# AMX30.net
KiCad netlist of a schematic drawn in Altium Designer
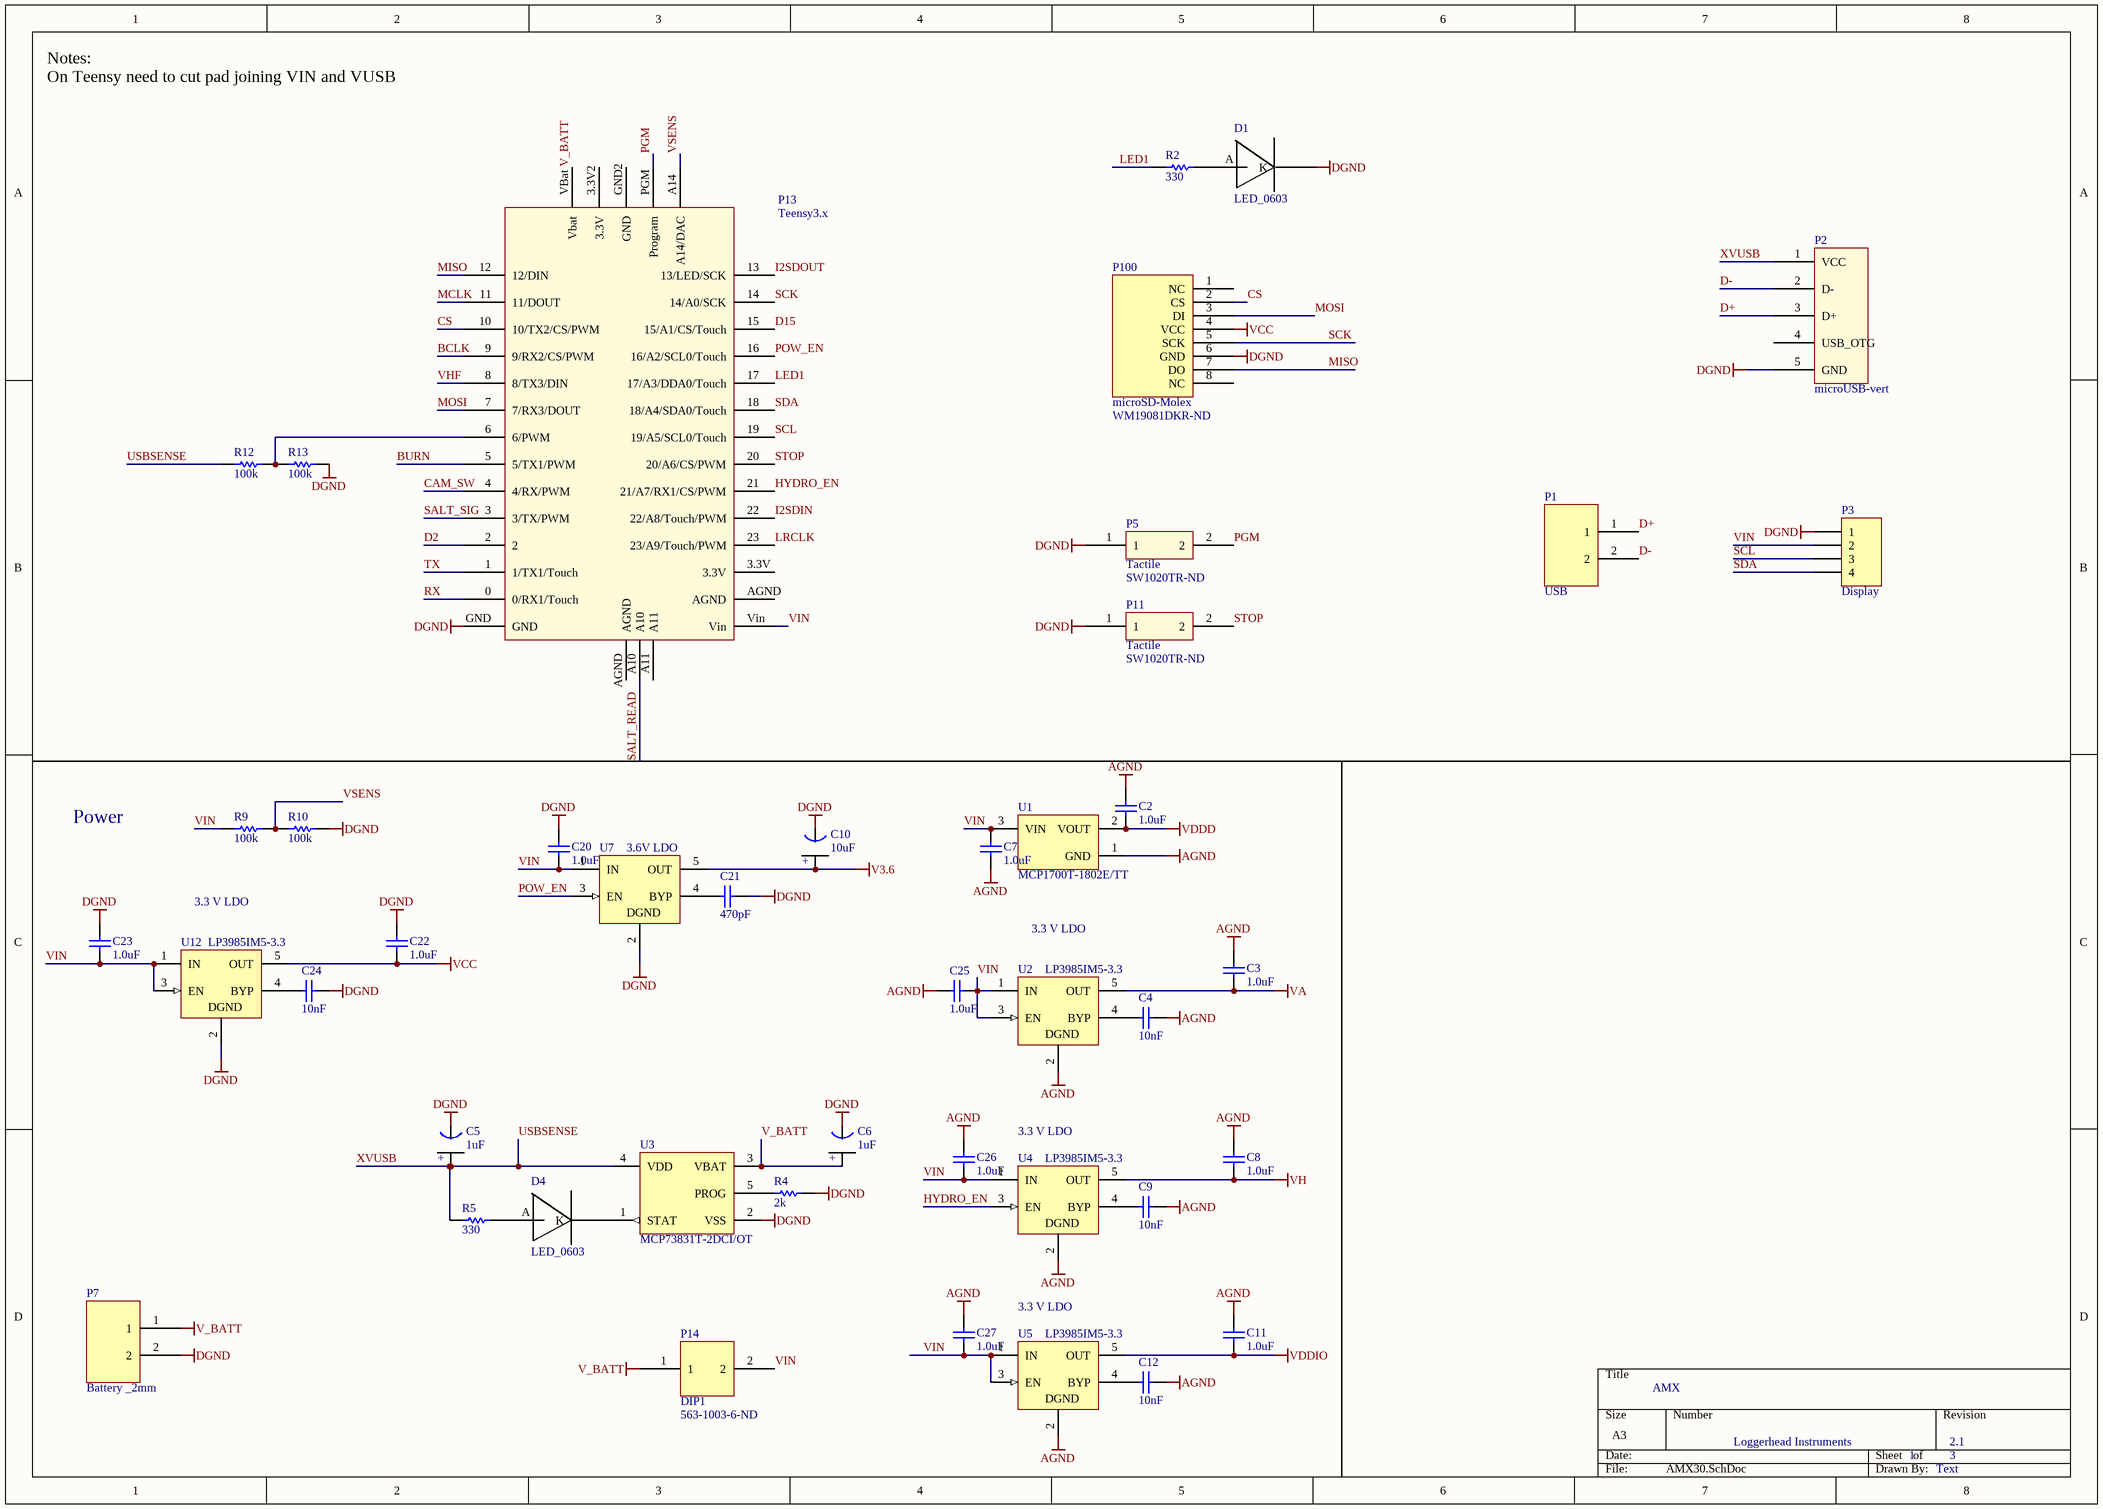
[diagram p0: AMX30.SchDoc]

(export (version "E")
  (design (tool "Eeschema 10.0.6"))
  (components
    (comp (ref "C2")
      (value "1.0uF")
      (footprint "0402")
      (description "Ceramic Chip Capacitor - Standard")
      (fields (field (name "PUBLISHER") "Altium Limited"))
      (libsource (lib "KEMET Chip Capacitor") (part "C0402"))
    )
    (comp (ref "C3")
      (value "1.0uF")
      (footprint "0402")
      (description "Ceramic Chip Capacitor - Standard")
      (fields (field (name "PUBLISHER") "Altium Limited"))
      (libsource (lib "KEMET Chip Capacitor") (part "C0402"))
    )
    (comp (ref "C4")
      (value "10nF")
      (footprint "0402")
      (description "Ceramic Chip Capacitor - Standard")
      (fields (field (name "PUBLISHER") "Altium Limited"))
      (libsource (lib "KEMET Chip Capacitor") (part "C0402"))
    )
    (comp (ref "C5") (value "1uF") (footprint "Tant0805") (libsource (lib "Loggerhead") (part "Tant0805")))
    (comp (ref "C6") (value "1uF") (footprint "Tant0805") (libsource (lib "Loggerhead") (part "Tant0805")))
    (comp (ref "C7")
      (value "1.0uF")
      (footprint "0402")
      (description "Ceramic Chip Capacitor - Standard")
      (fields (field (name "PUBLISHER") "Altium Limited"))
      (libsource (lib "KEMET Chip Capacitor") (part "C0402"))
    )
    (comp (ref "C8")
      (value "1.0uF")
      (footprint "0402")
      (description "Ceramic Chip Capacitor - Standard")
      (fields (field (name "PUBLISHER") "Altium Limited"))
      (libsource (lib "KEMET Chip Capacitor") (part "C0402"))
    )
    (comp (ref "C9")
      (value "10nF")
      (footprint "0402")
      (description "Ceramic Chip Capacitor - Standard")
      (fields (field (name "PUBLISHER") "Altium Limited"))
      (libsource (lib "KEMET Chip Capacitor") (part "C0402"))
    )
    (comp (ref "C10") (value "10uF") (footprint "Tant0805") (libsource (lib "Loggerhead") (part "Tant0805")))
    (comp (ref "C11")
      (value "1.0uF")
      (footprint "0402")
      (description "Ceramic Chip Capacitor - Standard")
      (fields (field (name "PUBLISHER") "Altium Limited"))
      (libsource (lib "KEMET Chip Capacitor") (part "C0402"))
    )
    (comp (ref "C12")
      (value "10nF")
      (footprint "0402")
      (description "Ceramic Chip Capacitor - Standard")
      (fields (field (name "PUBLISHER") "Altium Limited"))
      (libsource (lib "KEMET Chip Capacitor") (part "C0402"))
    )
    (comp (ref "C20")
      (value "1.0uF")
      (footprint "0402")
      (description "Ceramic Chip Capacitor - Standard")
      (fields (field (name "PUBLISHER") "Altium Limited"))
      (libsource (lib "KEMET Chip Capacitor") (part "C0402"))
    )
    (comp (ref "C21")
      (value "470pF")
      (footprint "0402")
      (description "Ceramic Chip Capacitor - Standard")
      (fields (field (name "PUBLISHER") "Altium Limited"))
      (libsource (lib "KEMET Chip Capacitor") (part "C0402"))
    )
    (comp (ref "C22")
      (value "1.0uF")
      (footprint "0402")
      (description "Ceramic Chip Capacitor - Standard")
      (fields (field (name "PUBLISHER") "Altium Limited"))
      (libsource (lib "KEMET Chip Capacitor") (part "C0402"))
    )
    (comp (ref "C23")
      (value "1.0uF")
      (footprint "0402")
      (description "Ceramic Chip Capacitor - Standard")
      (fields (field (name "PUBLISHER") "Altium Limited"))
      (libsource (lib "KEMET Chip Capacitor") (part "C0402"))
    )
    (comp (ref "C24")
      (value "10nF")
      (footprint "0402")
      (description "Ceramic Chip Capacitor - Standard")
      (fields (field (name "PUBLISHER") "Altium Limited"))
      (libsource (lib "KEMET Chip Capacitor") (part "C0402"))
    )
    (comp (ref "C25")
      (value "1.0uF")
      (footprint "0402")
      (description "Ceramic Chip Capacitor - Standard")
      (fields (field (name "PUBLISHER") "Altium Limited"))
      (libsource (lib "KEMET Chip Capacitor") (part "C0402"))
    )
    (comp (ref "C26")
      (value "1.0uF")
      (footprint "0402")
      (description "Ceramic Chip Capacitor - Standard")
      (fields (field (name "PUBLISHER") "Altium Limited"))
      (libsource (lib "KEMET Chip Capacitor") (part "C0402"))
    )
    (comp (ref "C27")
      (value "1.0uF")
      (footprint "0402")
      (description "Ceramic Chip Capacitor - Standard")
      (fields (field (name "PUBLISHER") "Altium Limited"))
      (libsource (lib "KEMET Chip Capacitor") (part "C0402"))
    )
    (comp (ref "D1")
      (value "LED_0603")
      (footprint "Diode0603")
      (libsource (lib "Loggerhead") (part "LED_0603"))
    )
    (comp (ref "D4")
      (value "LED_0603")
      (footprint "Diode0603")
      (libsource (lib "Loggerhead") (part "LED_0603"))
    )
    (comp (ref "P1")
      (value "USB")
      (footprint "HDR_2x1_2mm")
      (description "Charging Connector")
      (libsource (lib "Loggerhead") (part "HDR_2x1_2mm"))
    )
    (comp (ref "P2")
      (value "microUSB-vert")
      (footprint "MICROUSB-VERT")
      (description "Molex 105133-0011")
      (libsource (lib "Loggerhead") (part "microUSB-vert"))
    )
    (comp (ref "P3")
      (value "Display")
      (footprint "HDR1X4")
      (description "Header, 4-Pin")
      (fields (field (name "PUBLISHER") "Altium Limited"))
      (libsource (lib "Miscellaneous Connectors") (part "Header 4"))
    )
    (comp (ref "P5")
      (value "Tactile")
      (footprint "Tactile-B3U-1000")
      (fields (field (name "SUPPLIER PART NUMBER 1") "SW1020TR-ND"))
      (libsource (lib "Loggerhead") (part "Tactile_B3U-1000"))
    )
    (comp (ref "P7")
      (value "Battery _2mm")
      (footprint "HDR_2x1_2mm")
      (description "Charging Connector")
      (libsource (lib "Loggerhead") (part "HDR_2x1_2mm"))
    )
    (comp (ref "P11")
      (value "Tactile")
      (footprint "Tactile-B3U-1000")
      (fields (field (name "SUPPLIER PART NUMBER 1") "SW1020TR-ND"))
      (libsource (lib "Loggerhead") (part "Tactile_B3U-1000"))
    )
    (comp (ref "P13")
      (value "Teensy3.x")
      (footprint "Teensy3.x")
      (libsource (lib "Teensy") (part "Teensy3.x"))
    )
    (comp (ref "P14")
      (value "DIP1")
      (footprint "DIP1")
      (fields (field (name "SUPPLIER PART NUMBER 1") "563-1003-6-ND"))
      (libsource (lib "Loggerhead") (part "DIP1"))
    )
    (comp (ref "P100")
      (value "microSD-Molex")
      (footprint "microSD_Molex_hinged")
      (fields (field (name "SUPPLIER PART NUMBER 1") "WM19081DKR-ND"))
      (libsource (lib "Loggerhead") (part "microSD_Molex_hinged"))
    )
    (comp (ref "R2")
      (value "330")
      (footprint "3-0603")
      (fields (field (name "PUBLISHER") "Altium Limited"))
      (libsource (lib "Panasonic Resistor") (part "ERJ3RK"))
    )
    (comp (ref "R4")
      (value "2k")
      (footprint "3-0603")
      (fields (field (name "PUBLISHER") "Altium Limited"))
      (libsource (lib "Panasonic Resistor") (part "ERJ3RK"))
    )
    (comp (ref "R5")
      (value "330")
      (footprint "3-0603")
      (fields (field (name "PUBLISHER") "Altium Limited"))
      (libsource (lib "Panasonic Resistor") (part "ERJ3RK"))
    )
    (comp (ref "R9")
      (value "100k")
      (footprint "3-0603")
      (fields (field (name "PUBLISHER") "Altium Limited"))
      (libsource (lib "Panasonic Resistor") (part "ERJ3RK"))
    )
    (comp (ref "R10")
      (value "100k")
      (footprint "3-0603")
      (fields (field (name "PUBLISHER") "Altium Limited"))
      (libsource (lib "Panasonic Resistor") (part "ERJ3RK"))
    )
    (comp (ref "R12")
      (value "100k")
      (footprint "3-0603")
      (fields (field (name "PUBLISHER") "Altium Limited"))
      (libsource (lib "Panasonic Resistor") (part "ERJ3RK"))
    )
    (comp (ref "R13")
      (value "100k")
      (footprint "3-0603")
      (fields (field (name "PUBLISHER") "Altium Limited"))
      (libsource (lib "Panasonic Resistor") (part "ERJ3RK"))
    )
    (comp (ref "U1")
      (value "MCP1700T-1802E/TT")
      (footprint "SOT-23-TT3_N")
      (description "Low Quiescent Current LDO, 3-Pin SOT-23, Extended Temperature, Tape and Reel")
      (fields (field (name "MANUFACTURER") "Microchip"))
      (libsource (lib "Microchip Power Management Line Regulator") (part "MCP1700T-1802E/TT"))
    )
    (comp (ref "U2")
      (value "LP3985IM5-3.3")
      (footprint "MF05A_N")
      (description "Micropower, 150mA Low-Noise Ultra Low-Dropout CMOS Voltage Regulator")
      (fields
        (field (name "MANUFACTURER") "National Semiconductor")
        (field (name "DIGIKEYPARTNUMBER") "LP3985IM5-3.3CT-ND")
        (field (name "PUBLISHER") "Altium Limited")
      )
      (libsource (lib "NSC LDO") (part "LP3985IM5-3.3"))
    )
    (comp (ref "U3")
      (value "MCP73831T-2DCI/OT")
      (footprint "SOT-23-OT5_N")
      (libsource (lib "Microchip Power Management Battery Management") (part "MCP73831T-2DCI/OT"))
    )
    (comp (ref "U4")
      (value "LP3985IM5-3.3")
      (footprint "MF05A_N")
      (description "Micropower, 150mA Low-Noise Ultra Low-Dropout CMOS Voltage Regulator")
      (fields
        (field (name "MANUFACTURER") "National Semiconductor")
        (field (name "DIGIKEYPARTNUMBER") "LP3985IM5-3.3CT-ND")
        (field (name "PUBLISHER") "Altium Limited")
      )
      (libsource (lib "NSC LDO") (part "LP3985IM5-3.3"))
    )
    (comp (ref "U5")
      (value "LP3985IM5-3.3")
      (footprint "MF05A_N")
      (description "Micropower, 150mA Low-Noise Ultra Low-Dropout CMOS Voltage Regulator")
      (fields
        (field (name "MANUFACTURER") "National Semiconductor")
        (field (name "DIGIKEYPARTNUMBER") "LP3985IM5-3.3CT-ND")
        (field (name "PUBLISHER") "Altium Limited")
      )
      (libsource (lib "NSC LDO") (part "LP3985IM5-3.3"))
    )
    (comp (ref "U7")
      (value "3.6V LDO")
      (footprint "MF05A_N")
      (description "Micropower, 150mA Low-Noise Ultra Low-Dropout CMOS Voltage Regulator")
      (fields
        (field (name "PARTNUMBER") "LP3985IM5-3.3")
        (field (name "MANUFACTURER") "National Semiconductor")
        (field (name "PUBLISHER") "Altium Limited")
      )
      (libsource (lib "NSC LDO") (part "LP3985IM5-3.3"))
    )
    (comp (ref "U12")
      (value "LP3985IM5-3.3")
      (footprint "MF05A_N")
      (description "Micropower, 150mA Low-Noise Ultra Low-Dropout CMOS Voltage Regulator")
      (fields
        (field (name "MANUFACTURER") "National Semiconductor")
        (field (name "DIGIKEYPARTNUMBER") "LP3985IM5-3.3CT-ND")
        (field (name "PUBLISHER") "Altium Limited")
      )
      (libsource (lib "NSC LDO") (part "LP3985IM5-3.3"))
    )
  )
  (nets
    (net (code "1") (name "/BCLK") (class "Default")
      (node (ref "P13") (pin "9") (pinfunction "9/RX2/CS/PWM_9") (pintype "passive"))
    )
    (net (code "2") (name "/BURN") (class "Default")
      (node (ref "P13") (pin "5") (pinfunction "5/TX1/PWM_5") (pintype "passive"))
    )
    (net (code "3") (name "/CAM_SW") (class "Default")
      (node (ref "P13") (pin "4") (pinfunction "4/RX/PWM_4") (pintype "passive"))
    )
    (net (code "4") (name "/CS") (class "Default")
      (node (ref "P100") (pin "2") (pinfunction "CS_2") (pintype "passive"))
      (node (ref "P13") (pin "10") (pinfunction "10/TX2/CS/PWM_10") (pintype "passive"))
    )
    (net (code "5") (name "/D+") (class "Default")
      (node (ref "P1") (pin "1") (pinfunction "1_1") (pintype "passive"))
      (node (ref "P2") (pin "3") (pinfunction "D+_3") (pintype "passive"))
    )
    (net (code "6") (name "/D-") (class "Default")
      (node (ref "P1") (pin "2") (pinfunction "2_2") (pintype "passive"))
      (node (ref "P2") (pin "2") (pinfunction "D-_2") (pintype "passive"))
    )
    (net (code "7") (name "/D2") (class "Default")
      (node (ref "P13") (pin "2") (pinfunction "2_2") (pintype "passive"))
    )
    (net (code "8") (name "/D15") (class "Default")
      (node (ref "P13") (pin "15") (pinfunction "15/A1/CS/Touch_15") (pintype "passive"))
    )
    (net (code "9") (name "/HYDRO_EN") (class "Default")
      (node (ref "P13") (pin "21") (pinfunction "21/A7/RX1/CS/PWM_21") (pintype "passive"))
      (node (ref "U4") (pin "3") (pinfunction "EN_3") (pintype "input"))
    )
    (net (code "10") (name "/I2SDIN") (class "Default")
      (node (ref "P13") (pin "22") (pinfunction "22/A8/Touch/PWM_22") (pintype "passive"))
    )
    (net (code "11") (name "/I2SDOUT") (class "Default")
      (node (ref "P13") (pin "13") (pinfunction "13/LED/SCK_13") (pintype "passive"))
    )
    (net (code "12") (name "/LED1") (class "Default")
      (node (ref "P13") (pin "17") (pinfunction "17/A3/DDA0/Touch_17") (pintype "passive"))
      (node (ref "R2") (pin "1") (pinfunction "1_1") (pintype "passive"))
    )
    (net (code "13") (name "/LRCLK") (class "Default")
      (node (ref "P13") (pin "23") (pinfunction "23/A9/Touch/PWM_23") (pintype "passive"))
    )
    (net (code "14") (name "/MCLK") (class "Default")
      (node (ref "P13") (pin "11") (pinfunction "11/DOUT_11") (pintype "passive"))
    )
    (net (code "15") (name "/MISO") (class "Default")
      (node (ref "P100") (pin "7") (pinfunction "DO_7") (pintype "passive"))
      (node (ref "P13") (pin "12") (pinfunction "12/DIN_12") (pintype "passive"))
    )
    (net (code "16") (name "/MOSI") (class "Default")
      (node (ref "P100") (pin "3") (pinfunction "DI_3") (pintype "passive"))
      (node (ref "P13") (pin "7") (pinfunction "7/RX3/DOUT_7") (pintype "passive"))
    )
    (net (code "17") (name "/PGM") (class "Default")
      (node (ref "P13") (pin "PGM") (pinfunction "Program_PGM") (pintype "passive"))
      (node (ref "P5") (pin "2") (pinfunction "2_2") (pintype "passive"))
    )
    (net (code "18") (name "/POW_EN") (class "Default")
      (node (ref "P13") (pin "16") (pinfunction "16/A2/SCL0/Touch_16") (pintype "passive"))
      (node (ref "U7") (pin "3") (pinfunction "EN_3") (pintype "input"))
    )
    (net (code "19") (name "/RX") (class "Default")
      (node (ref "P13") (pin "0") (pinfunction "0/RX1/Touch_0") (pintype "passive"))
    )
    (net (code "20") (name "/SALT_READ") (class "Default")
      (node (ref "P13") (pin "A10") (pinfunction "A10_A10") (pintype "passive"))
    )
    (net (code "21") (name "/SALT_SIG") (class "Default")
      (node (ref "P13") (pin "3") (pinfunction "3/TX/PWM_3") (pintype "passive"))
    )
    (net (code "22") (name "/SCK") (class "Default")
      (node (ref "P100") (pin "5") (pinfunction "SCK_5") (pintype "passive"))
      (node (ref "P13") (pin "14") (pinfunction "14/A0/SCK_14") (pintype "passive"))
    )
    (net (code "23") (name "/SCL") (class "Default")
      (node (ref "P13") (pin "19") (pinfunction "19/A5/SCL0/Touch_19") (pintype "passive"))
      (node (ref "P3") (pin "3") (pinfunction "3_3") (pintype "passive"))
    )
    (net (code "24") (name "/SDA") (class "Default")
      (node (ref "P13") (pin "18") (pinfunction "18/A4/SDA0/Touch_18") (pintype "passive"))
      (node (ref "P3") (pin "4") (pinfunction "4_4") (pintype "passive"))
    )
    (net (code "25") (name "/STOP") (class "Default")
      (node (ref "P11") (pin "2") (pinfunction "2_2") (pintype "passive"))
      (node (ref "P13") (pin "20") (pinfunction "20/A6/CS/PWM_20") (pintype "passive"))
    )
    (net (code "26") (name "/TX") (class "Default")
      (node (ref "P13") (pin "1") (pinfunction "1/TX1/Touch_1") (pintype "passive"))
    )
    (net (code "27") (name "/USBSENSE") (class "Default")
      (node (ref "C5") (pin "2") (pinfunction "+_2") (pintype "passive"))
      (node (ref "P2") (pin "1") (pinfunction "VCC_1") (pintype "passive"))
      (node (ref "R12") (pin "1") (pinfunction "1_1") (pintype "passive"))
      (node (ref "R5") (pin "1") (pinfunction "1_1") (pintype "passive"))
      (node (ref "U3") (pin "4") (pinfunction "VDD_4") (pintype "power_in"))
    )
    (net (code "28") (name "/VHF") (class "Default")
      (node (ref "P13") (pin "8") (pinfunction "8/TX3/DIN_8") (pintype "passive"))
    )
    (net (code "29") (name "/VIN") (class "Default")
      (node (ref "C20") (pin "1") (pinfunction "1_1") (pintype "passive"))
      (node (ref "C23") (pin "1") (pinfunction "1_1") (pintype "passive"))
      (node (ref "C25") (pin "1") (pinfunction "1_1") (pintype "passive"))
      (node (ref "C26") (pin "1") (pinfunction "1_1") (pintype "passive"))
      (node (ref "C27") (pin "1") (pinfunction "1_1") (pintype "passive"))
      (node (ref "C7") (pin "1") (pinfunction "1_1") (pintype "passive"))
      (node (ref "P13") (pin "Vin") (pinfunction "Vin_Vin") (pintype "passive"))
      (node (ref "P14") (pin "2") (pinfunction "2_2") (pintype "passive"))
      (node (ref "P3") (pin "2") (pinfunction "2_2") (pintype "passive"))
      (node (ref "R9") (pin "2") (pinfunction "2_2") (pintype "passive"))
      (node (ref "U1") (pin "3") (pinfunction "VIN_3") (pintype "power_in"))
      (node (ref "U12") (pin "1") (pinfunction "IN_1") (pintype "power_in"))
      (node (ref "U12") (pin "3") (pinfunction "EN_3") (pintype "input"))
      (node (ref "U2") (pin "1") (pinfunction "IN_1") (pintype "power_in"))
      (node (ref "U2") (pin "3") (pinfunction "EN_3") (pintype "input"))
      (node (ref "U4") (pin "1") (pinfunction "IN_1") (pintype "power_in"))
      (node (ref "U5") (pin "1") (pinfunction "IN_1") (pintype "power_in"))
      (node (ref "U5") (pin "3") (pinfunction "EN_3") (pintype "input"))
      (node (ref "U7") (pin "1") (pinfunction "IN_1") (pintype "power_in"))
    )
    (net (code "30") (name "/VSENS") (class "Default")
      (node (ref "P13") (pin "A14") (pinfunction "A14/DAC_A14") (pintype "passive"))
      (node (ref "R10") (pin "2") (pinfunction "2_2") (pintype "passive"))
      (node (ref "R9") (pin "1") (pinfunction "1_1") (pintype "passive"))
    )
    (net (code "31") (name "AGND") (class "Default")
      (node (ref "C11") (pin "2") (pinfunction "2_2") (pintype "passive"))
      (node (ref "C12") (pin "1") (pinfunction "1_1") (pintype "passive"))
      (node (ref "C2") (pin "2") (pinfunction "2_2") (pintype "passive"))
      (node (ref "C25") (pin "2") (pinfunction "2_2") (pintype "passive"))
      (node (ref "C26") (pin "2") (pinfunction "2_2") (pintype "passive"))
      (node (ref "C27") (pin "2") (pinfunction "2_2") (pintype "passive"))
      (node (ref "C3") (pin "2") (pinfunction "2_2") (pintype "passive"))
      (node (ref "C4") (pin "1") (pinfunction "1_1") (pintype "passive"))
      (node (ref "C7") (pin "2") (pinfunction "2_2") (pintype "passive"))
      (node (ref "C8") (pin "2") (pinfunction "2_2") (pintype "passive"))
      (node (ref "C9") (pin "1") (pinfunction "1_1") (pintype "passive"))
      (node (ref "U1") (pin "1") (pinfunction "GND_1") (pintype "power_in"))
      (node (ref "U2") (pin "2") (pinfunction "GND_2") (pintype "power_in"))
      (node (ref "U4") (pin "2") (pinfunction "GND_2") (pintype "power_in"))
      (node (ref "U5") (pin "2") (pinfunction "GND_2") (pintype "power_in"))
    )
    (net (code "32") (name "DGND") (class "Default")
      (node (ref "C10") (pin "1") (pinfunction "GND_1") (pintype "passive"))
      (node (ref "C20") (pin "2") (pinfunction "2_2") (pintype "passive"))
      (node (ref "C21") (pin "1") (pinfunction "1_1") (pintype "passive"))
      (node (ref "C22") (pin "2") (pinfunction "2_2") (pintype "passive"))
      (node (ref "C23") (pin "2") (pinfunction "2_2") (pintype "passive"))
      (node (ref "C24") (pin "1") (pinfunction "1_1") (pintype "passive"))
      (node (ref "C5") (pin "1") (pinfunction "GND_1") (pintype "passive"))
      (node (ref "C6") (pin "1") (pinfunction "GND_1") (pintype "passive"))
      (node (ref "D1") (pin "K") (pinfunction "K_K") (pintype "passive"))
      (node (ref "P100") (pin "6") (pinfunction "GND_6") (pintype "passive"))
      (node (ref "P11") (pin "1") (pinfunction "1_1") (pintype "passive"))
      (node (ref "P13") (pin "GND") (pinfunction "GND_GND") (pintype "passive"))
      (node (ref "P2") (pin "5") (pinfunction "GND_5") (pintype "passive"))
      (node (ref "P3") (pin "1") (pinfunction "1_1") (pintype "passive"))
      (node (ref "P5") (pin "1") (pinfunction "1_1") (pintype "passive"))
      (node (ref "P7") (pin "2") (pinfunction "2_2") (pintype "passive"))
      (node (ref "R10") (pin "1") (pinfunction "1_1") (pintype "passive"))
      (node (ref "R13") (pin "2") (pinfunction "2_2") (pintype "passive"))
      (node (ref "R4") (pin "1") (pinfunction "1_1") (pintype "passive"))
      (node (ref "U12") (pin "2") (pinfunction "GND_2") (pintype "power_in"))
      (node (ref "U3") (pin "2") (pinfunction "VSS_2") (pintype "power_in"))
      (node (ref "U7") (pin "2") (pinfunction "GND_2") (pintype "power_in"))
    )
    (net (code "33") (name "Net-(D1-PadA)") (class "Default")
      (node (ref "D1") (pin "A") (pinfunction "A_A") (pintype "passive"))
      (node (ref "R2") (pin "2") (pinfunction "2_2") (pintype "passive"))
    )
    (net (code "34") (name "Net-(D4-PadA)") (class "Default")
      (node (ref "D4") (pin "A") (pinfunction "A_A") (pintype "passive"))
      (node (ref "R5") (pin "2") (pinfunction "2_2") (pintype "passive"))
    )
    (net (code "35") (name "Net-(P13-6{slash}PWM)") (class "Default")
      (node (ref "P13") (pin "6") (pinfunction "6/PWM_6") (pintype "passive"))
      (node (ref "R12") (pin "2") (pinfunction "2_2") (pintype "passive"))
      (node (ref "R13") (pin "1") (pinfunction "1_1") (pintype "passive"))
    )
    (net (code "36") (name "Net-(U2-BYP)") (class "Default")
      (node (ref "C4") (pin "2") (pinfunction "2_2") (pintype "passive"))
      (node (ref "U2") (pin "4") (pinfunction "BYP_4") (pintype "passive"))
    )
    (net (code "37") (name "Net-(U3-PROG)") (class "Default")
      (node (ref "R4") (pin "2") (pinfunction "2_2") (pintype "passive"))
      (node (ref "U3") (pin "5") (pinfunction "PROG_5") (pintype "passive"))
    )
    (net (code "38") (name "Net-(U3-STAT)") (class "Default")
      (node (ref "D4") (pin "K") (pinfunction "K_K") (pintype "passive"))
      (node (ref "U3") (pin "1") (pinfunction "STAT_1") (pintype "output"))
    )
    (net (code "39") (name "Net-(U4-BYP)") (class "Default")
      (node (ref "C9") (pin "2") (pinfunction "2_2") (pintype "passive"))
      (node (ref "U4") (pin "4") (pinfunction "BYP_4") (pintype "passive"))
    )
    (net (code "40") (name "Net-(U5-BYP)") (class "Default")
      (node (ref "C12") (pin "2") (pinfunction "2_2") (pintype "passive"))
      (node (ref "U5") (pin "4") (pinfunction "BYP_4") (pintype "passive"))
    )
    (net (code "41") (name "Net-(U7-BYP)") (class "Default")
      (node (ref "C21") (pin "2") (pinfunction "2_2") (pintype "passive"))
      (node (ref "U7") (pin "4") (pinfunction "BYP_4") (pintype "passive"))
    )
    (net (code "42") (name "Net-(U12-BYP)") (class "Default")
      (node (ref "C24") (pin "2") (pinfunction "2_2") (pintype "passive"))
      (node (ref "U12") (pin "4") (pinfunction "BYP_4") (pintype "passive"))
    )
    (net (code "43") (name "V3.6") (class "Default")
      (node (ref "C10") (pin "2") (pinfunction "+_2") (pintype "passive"))
      (node (ref "U7") (pin "5") (pinfunction "OUT_5") (pintype "power_in"))
    )
    (net (code "44") (name "VA") (class "Default")
      (node (ref "C3") (pin "1") (pinfunction "1_1") (pintype "passive"))
      (node (ref "U2") (pin "5") (pinfunction "OUT_5") (pintype "power_in"))
    )
    (net (code "45") (name "VCC") (class "Default")
      (node (ref "C22") (pin "1") (pinfunction "1_1") (pintype "passive"))
      (node (ref "P100") (pin "4") (pinfunction "VCC_4") (pintype "passive"))
      (node (ref "U12") (pin "5") (pinfunction "OUT_5") (pintype "power_in"))
    )
    (net (code "46") (name "VDDD") (class "Default")
      (node (ref "C2") (pin "1") (pinfunction "1_1") (pintype "passive"))
      (node (ref "U1") (pin "2") (pinfunction "VOUT_2") (pintype "power_in"))
    )
    (net (code "47") (name "VDDIO") (class "Default")
      (node (ref "C11") (pin "1") (pinfunction "1_1") (pintype "passive"))
      (node (ref "U5") (pin "5") (pinfunction "OUT_5") (pintype "power_in"))
    )
    (net (code "48") (name "VH") (class "Default")
      (node (ref "C8") (pin "1") (pinfunction "1_1") (pintype "passive"))
      (node (ref "U4") (pin "5") (pinfunction "OUT_5") (pintype "power_in"))
    )
    (net (code "49") (name "V_BATT") (class "Default")
      (node (ref "C6") (pin "2") (pinfunction "+_2") (pintype "passive"))
      (node (ref "P13") (pin "VBat") (pinfunction "Vbat_VBat") (pintype "passive"))
      (node (ref "P14") (pin "1") (pinfunction "1_1") (pintype "passive"))
      (node (ref "P7") (pin "1") (pinfunction "1_1") (pintype "passive"))
      (node (ref "U3") (pin "3") (pinfunction "VBAT_3") (pintype "power_in"))
    )
    (net (code "50") (name "unconnected-(P2-USB_OTG-Pad4)") (class "Default")
      (node (ref "P2") (pin "4") (pinfunction "USB_OTG_4") (pintype "passive"))
    )
    (net (code "51") (name "unconnected-(P13-3.3V-Pad3.3V2)") (class "Default")
      (node (ref "P13") (pin "3.3V2") (pinfunction "3.3V_3.3V2") (pintype "passive"))
    )
    (net (code "52") (name "unconnected-(P13-GND-PadGND2)") (class "Default")
      (node (ref "P13") (pin "GND2") (pinfunction "GND_GND2") (pintype "passive"))
    )
    (net (code "53") (name "unconnected-(P13-Pad3.3V)") (class "Default")
      (node (ref "P13") (pin "3.3V") (pinfunction "3.3V_3.3V") (pintype "passive"))
    )
    (net (code "54") (name "unconnected-(P13-PadA11)") (class "Default")
      (node (ref "P13") (pin "A11") (pinfunction "A11_A11") (pintype "passive"))
    )
    (net (code "55") (name "unconnected-(P13-PadAGND)") (class "Default")
      (node (ref "P13") (pin "AGND") (pinfunction "AGND_AGND") (pintype "passive"))
    )
    (net (code "56") (name "unconnected-(P13-PadAGND)_1") (class "Default")
      (node (ref "P13") (pin "AGND") (pinfunction "AGND_AGND") (pintype "passive"))
    )
    (net (code "57") (name "unconnected-(P100-NC-Pad1)") (class "Default")
      (node (ref "P100") (pin "1") (pinfunction "NC_1") (pintype "passive"))
    )
    (net (code "58") (name "unconnected-(P100-NC-Pad8)") (class "Default")
      (node (ref "P100") (pin "8") (pinfunction "NC_8") (pintype "passive"))
    )
  )
)
